# config-power.net
KiCad netlist of a schematic drawn in Altium Designer
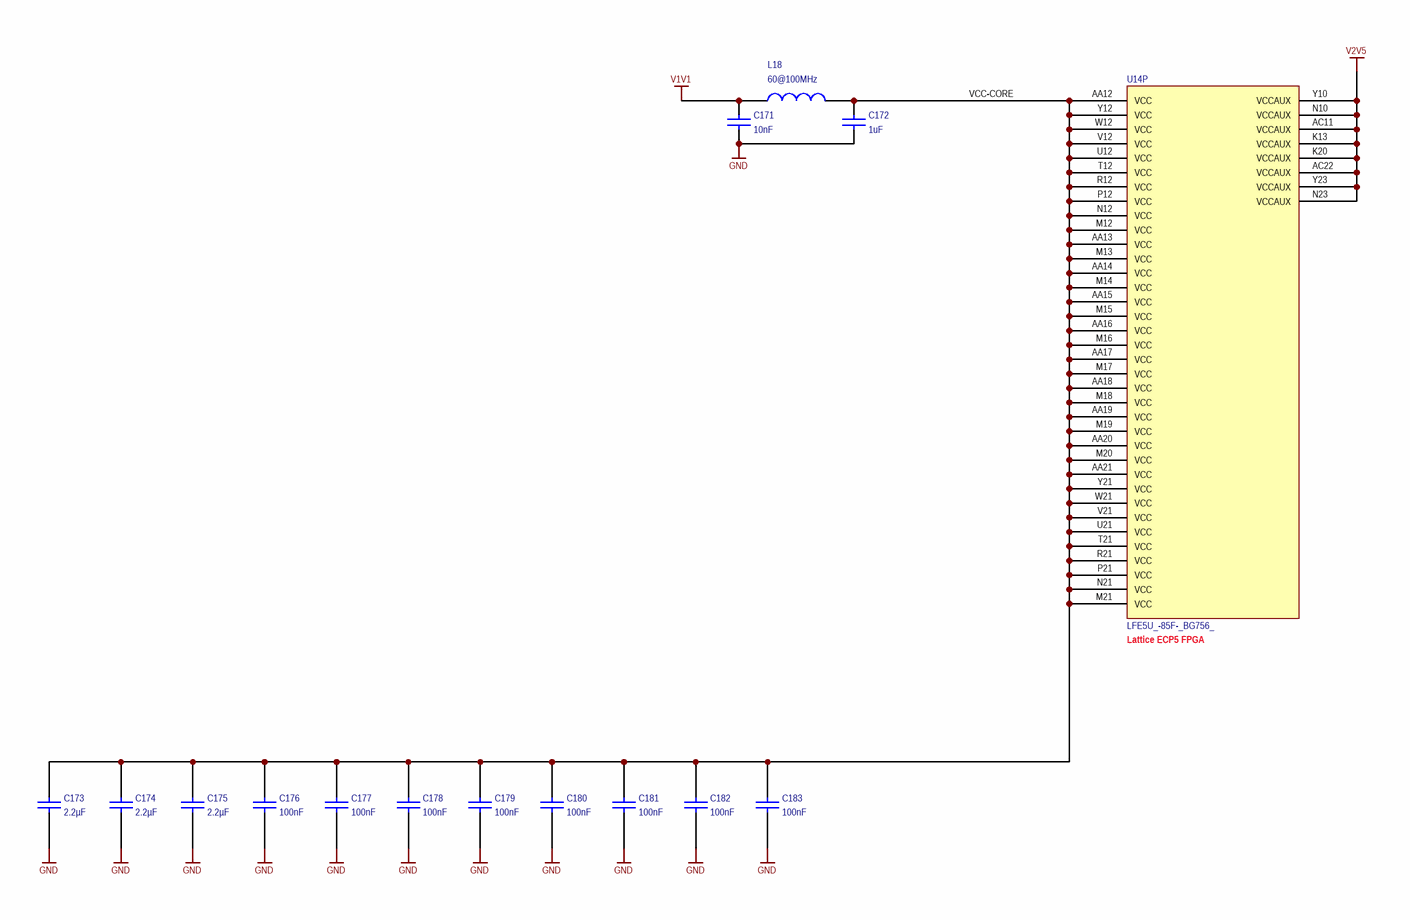
[diagram p0: config-power.SchDoc]

(export (version "E")
  (design (tool "Eeschema 10.0.6"))
  (components
    (comp (ref "C171")
      (value "10nF")
      (footprint "generic:0402")
      (description "Ceramic Capacitor 10nF ±10% 25V X7R 0402")
      (fields (field (name "VOLTAGE") "25V") (field (name "MANUFACTURER") "Murata"))
      (libsource (lib "Graviton") (part "CAP 0402"))
    )
    (comp (ref "C172")
      (value "1uF")
      (footprint "generic:0402")
      (description "Ceramic Capacitor 1uF ±10% 10V X5R 0402")
      (fields (field (name "VOLTAGE") "10V") (field (name "MANUFACTURER") "Murata"))
      (libsource (lib "Graviton") (part "CAP 0402"))
    )
    (comp (ref "C173")
      (value "2.2µF")
      (footprint "generic:CAPC1608X90N")
      (description "Ceramic Capacitor 2.2uF ±10% 10V X7R 0603")
      (fields (field (name "MANUFACTURER") "Murata") (field (name "TOLERANCE") "±10%"))
      (libsource (lib "murata") (part "GRM188R71A225KE15D"))
    )
    (comp (ref "C174")
      (value "2.2µF")
      (footprint "generic:CAPC1608X90N")
      (description "Ceramic Capacitor 2.2uF ±10% 10V X7R 0603")
      (fields (field (name "MANUFACTURER") "Murata") (field (name "TOLERANCE") "±10%"))
      (libsource (lib "murata") (part "GRM188R71A225KE15D"))
    )
    (comp (ref "C175")
      (value "2.2µF")
      (footprint "generic:CAPC1608X90N")
      (description "Ceramic Capacitor 2.2uF ±10% 10V X7R 0603")
      (fields (field (name "MANUFACTURER") "Murata") (field (name "TOLERANCE") "±10%"))
      (libsource (lib "murata") (part "GRM188R71A225KE15D"))
    )
    (comp (ref "C176")
      (value "100nF")
      (footprint "generic:CAPC1005X56N")
      (description "Ceramic Capacitor 100nF ±10% 16V X7R 0402")
      (fields (field (name "MANUFACTURER") "Murata") (field (name "TOLERANCE") "±10%"))
      (libsource (lib "murata") (part "GRM155R71A104KA01J"))
    )
    (comp (ref "C177")
      (value "100nF")
      (footprint "generic:CAPC1005X56N")
      (description "Ceramic Capacitor 100nF ±10% 16V X7R 0402")
      (fields (field (name "MANUFACTURER") "Murata") (field (name "TOLERANCE") "±10%"))
      (libsource (lib "murata") (part "GRM155R71A104KA01J"))
    )
    (comp (ref "C178")
      (value "100nF")
      (footprint "generic:CAPC1005X56N")
      (description "Ceramic Capacitor 100nF ±10% 16V X7R 0402")
      (fields (field (name "MANUFACTURER") "Murata") (field (name "TOLERANCE") "±10%"))
      (libsource (lib "murata") (part "GRM155R71A104KA01J"))
    )
    (comp (ref "C179")
      (value "100nF")
      (footprint "generic:CAPC1005X56N")
      (description "Ceramic Capacitor 100nF ±10% 16V X7R 0402")
      (fields (field (name "MANUFACTURER") "Murata") (field (name "TOLERANCE") "±10%"))
      (libsource (lib "murata") (part "GRM155R71A104KA01J"))
    )
    (comp (ref "C180")
      (value "100nF")
      (footprint "generic:CAPC1005X56N")
      (description "Ceramic Capacitor 100nF ±10% 16V X7R 0402")
      (fields (field (name "MANUFACTURER") "Murata") (field (name "TOLERANCE") "±10%"))
      (libsource (lib "murata") (part "GRM155R71A104KA01J"))
    )
    (comp (ref "C181")
      (value "100nF")
      (footprint "generic:CAPC1005X56N")
      (description "Ceramic Capacitor 100nF ±10% 16V X7R 0402")
      (fields (field (name "MANUFACTURER") "Murata") (field (name "TOLERANCE") "±10%"))
      (libsource (lib "murata") (part "GRM155R71A104KA01J"))
    )
    (comp (ref "C182")
      (value "100nF")
      (footprint "generic:CAPC1005X56N")
      (description "Ceramic Capacitor 100nF ±10% 16V X7R 0402")
      (fields (field (name "MANUFACTURER") "Murata") (field (name "TOLERANCE") "±10%"))
      (libsource (lib "murata") (part "GRM155R71A104KA01J"))
    )
    (comp (ref "C183")
      (value "100nF")
      (footprint "generic:CAPC1005X56N")
      (description "Ceramic Capacitor 100nF ±10% 16V X7R 0402")
      (fields (field (name "MANUFACTURER") "Murata") (field (name "TOLERANCE") "±10%"))
      (libsource (lib "murata") (part "GRM155R71A104KA01J"))
    )
    (comp (ref "L18")
      (value "60@100MHz")
      (footprint "0402")
      (description "Ferrite Bead 60-Ohm @ 100MHz 2.5A 0402")
      (fields (field (name "MANUFACTURER") "Murata") (field (name "TOLERANCE") "±25%"))
      (libsource (lib "Graviton") (part "IND 0402"))
    )
    (comp (ref "U14")
      (value "LFE5U_-85F-_BG756_")
      (footprint "lattice:caBGA756")
      (description "ECP5 FPGA, 85k LUT, 756-caBGA")
      (fields (field (name "MANUFACTURER") "Lattice Semiconductor"))
      (libsource (lib "lattice") (part "LFE5U_-85F-_BG756_"))
    )
  )
  (nets
    (net (code "1") (name "/VCC-CORE") (class "Default")
      (node (ref "C172") (pin "2") (pinfunction "2_2") (pintype "passive"))
      (node (ref "C173") (pin "2") (pinfunction "2_2") (pintype "passive"))
      (node (ref "C174") (pin "2") (pinfunction "2_2") (pintype "passive"))
      (node (ref "C175") (pin "2") (pinfunction "2_2") (pintype "passive"))
      (node (ref "C176") (pin "2") (pinfunction "2_2") (pintype "passive"))
      (node (ref "C177") (pin "2") (pinfunction "2_2") (pintype "passive"))
      (node (ref "C178") (pin "2") (pinfunction "2_2") (pintype "passive"))
      (node (ref "C179") (pin "2") (pinfunction "2_2") (pintype "passive"))
      (node (ref "C180") (pin "2") (pinfunction "2_2") (pintype "passive"))
      (node (ref "C181") (pin "2") (pinfunction "2_2") (pintype "passive"))
      (node (ref "C182") (pin "2") (pinfunction "2_2") (pintype "passive"))
      (node (ref "C183") (pin "2") (pinfunction "2_2") (pintype "passive"))
      (node (ref "L18") (pin "2") (pinfunction "2_2") (pintype "passive"))
      (node (ref "U14") (pin "AA12") (pinfunction "VCC_AA12") (pintype "power_in"))
      (node (ref "U14") (pin "AA13") (pinfunction "VCC_AA13") (pintype "power_in"))
      (node (ref "U14") (pin "AA14") (pinfunction "VCC_AA14") (pintype "power_in"))
      (node (ref "U14") (pin "AA15") (pinfunction "VCC_AA15") (pintype "power_in"))
      (node (ref "U14") (pin "AA16") (pinfunction "VCC_AA16") (pintype "power_in"))
      (node (ref "U14") (pin "AA17") (pinfunction "VCC_AA17") (pintype "power_in"))
      (node (ref "U14") (pin "AA18") (pinfunction "VCC_AA18") (pintype "power_in"))
      (node (ref "U14") (pin "AA19") (pinfunction "VCC_AA19") (pintype "power_in"))
      (node (ref "U14") (pin "AA20") (pinfunction "VCC_AA20") (pintype "power_in"))
      (node (ref "U14") (pin "AA21") (pinfunction "VCC_AA21") (pintype "power_in"))
      (node (ref "U14") (pin "M12") (pinfunction "VCC_M12") (pintype "power_in"))
      (node (ref "U14") (pin "M13") (pinfunction "VCC_M13") (pintype "power_in"))
      (node (ref "U14") (pin "M14") (pinfunction "VCC_M14") (pintype "power_in"))
      (node (ref "U14") (pin "M15") (pinfunction "VCC_M15") (pintype "power_in"))
      (node (ref "U14") (pin "M16") (pinfunction "VCC_M16") (pintype "power_in"))
      (node (ref "U14") (pin "M17") (pinfunction "VCC_M17") (pintype "power_in"))
      (node (ref "U14") (pin "M18") (pinfunction "VCC_M18") (pintype "power_in"))
      (node (ref "U14") (pin "M19") (pinfunction "VCC_M19") (pintype "power_in"))
      (node (ref "U14") (pin "M20") (pinfunction "VCC_M20") (pintype "power_in"))
      (node (ref "U14") (pin "M21") (pinfunction "VCC_M21") (pintype "power_in"))
      (node (ref "U14") (pin "N12") (pinfunction "VCC_N12") (pintype "power_in"))
      (node (ref "U14") (pin "N21") (pinfunction "VCC_N21") (pintype "power_in"))
      (node (ref "U14") (pin "P12") (pinfunction "VCC_P12") (pintype "power_in"))
      (node (ref "U14") (pin "P21") (pinfunction "VCC_P21") (pintype "power_in"))
      (node (ref "U14") (pin "R12") (pinfunction "VCC_R12") (pintype "power_in"))
      (node (ref "U14") (pin "R21") (pinfunction "VCC_R21") (pintype "power_in"))
      (node (ref "U14") (pin "T12") (pinfunction "VCC_T12") (pintype "power_in"))
      (node (ref "U14") (pin "T21") (pinfunction "VCC_T21") (pintype "power_in"))
      (node (ref "U14") (pin "U12") (pinfunction "VCC_U12") (pintype "power_in"))
      (node (ref "U14") (pin "U21") (pinfunction "VCC_U21") (pintype "power_in"))
      (node (ref "U14") (pin "V12") (pinfunction "VCC_V12") (pintype "power_in"))
      (node (ref "U14") (pin "V21") (pinfunction "VCC_V21") (pintype "power_in"))
      (node (ref "U14") (pin "W12") (pinfunction "VCC_W12") (pintype "power_in"))
      (node (ref "U14") (pin "W21") (pinfunction "VCC_W21") (pintype "power_in"))
      (node (ref "U14") (pin "Y12") (pinfunction "VCC_Y12") (pintype "power_in"))
      (node (ref "U14") (pin "Y21") (pinfunction "VCC_Y21") (pintype "power_in"))
    )
    (net (code "2") (name "GND") (class "Default")
      (node (ref "C171") (pin "1") (pinfunction "1_1") (pintype "passive"))
      (node (ref "C172") (pin "1") (pinfunction "1_1") (pintype "passive"))
      (node (ref "C173") (pin "1") (pinfunction "1_1") (pintype "passive"))
      (node (ref "C174") (pin "1") (pinfunction "1_1") (pintype "passive"))
      (node (ref "C175") (pin "1") (pinfunction "1_1") (pintype "passive"))
      (node (ref "C176") (pin "1") (pinfunction "1_1") (pintype "passive"))
      (node (ref "C177") (pin "1") (pinfunction "1_1") (pintype "passive"))
      (node (ref "C178") (pin "1") (pinfunction "1_1") (pintype "passive"))
      (node (ref "C179") (pin "1") (pinfunction "1_1") (pintype "passive"))
      (node (ref "C180") (pin "1") (pinfunction "1_1") (pintype "passive"))
      (node (ref "C181") (pin "1") (pinfunction "1_1") (pintype "passive"))
      (node (ref "C182") (pin "1") (pinfunction "1_1") (pintype "passive"))
      (node (ref "C183") (pin "1") (pinfunction "1_1") (pintype "passive"))
    )
    (net (code "3") (name "V1V1") (class "Default")
      (node (ref "C171") (pin "2") (pinfunction "2_2") (pintype "passive"))
      (node (ref "L18") (pin "1") (pinfunction "1_1") (pintype "passive"))
    )
    (net (code "4") (name "V2V5") (class "Default")
      (node (ref "U14") (pin "AC11") (pinfunction "VCCAUX_AC11") (pintype "power_in"))
      (node (ref "U14") (pin "AC22") (pinfunction "VCCAUX_AC22") (pintype "power_in"))
      (node (ref "U14") (pin "K13") (pinfunction "VCCAUX_K13") (pintype "power_in"))
      (node (ref "U14") (pin "K20") (pinfunction "VCCAUX_K20") (pintype "power_in"))
      (node (ref "U14") (pin "N10") (pinfunction "VCCAUX_N10") (pintype "power_in"))
      (node (ref "U14") (pin "N23") (pinfunction "VCCAUX_N23") (pintype "power_in"))
      (node (ref "U14") (pin "Y10") (pinfunction "VCCAUX_Y10") (pintype "power_in"))
      (node (ref "U14") (pin "Y23") (pinfunction "VCCAUX_Y23") (pintype "power_in"))
    )
  )
)
